# RV-3028.net
KiCad netlist of a schematic drawn in Altium Designer
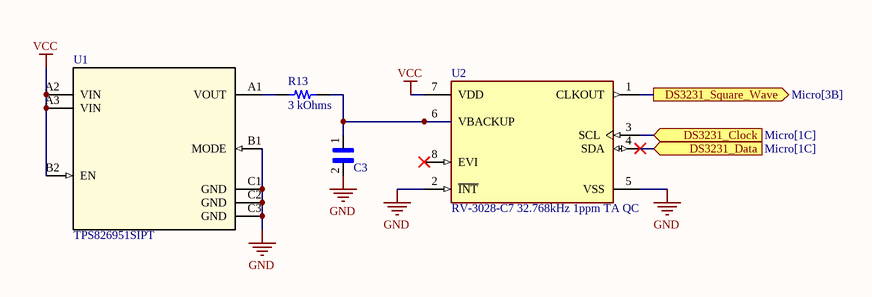
[diagram p0: RV-3028.SchDoc]

(export (version "E")
  (design (tool "Eeschema 10.0.6"))
  (components
    (comp (ref "C3")
      (value "CPX3225A752D")
      (footprint "CAPCP3225X100N")
      (description "7.5mF (EDLC) Supercapacitor 2.6V 1210 (3225 Metric) 25Ohm @ 1kHz")
      (fields (field (name "MF") "Seiko Instruments"))
      (libsource (lib "CPX3225A752D") (part "CPX3225A752D"))
    )
    (comp (ref "R13")
      (value "3 kOhms")
      (footprint "RES 0402_1005")
      (description "RES 3K OHM 1% 1/16W 0402")
      (fields (field (name "PART NUMBER") "RC0402FR-073KL") (field (name "MANUFACTURER") "Yageo"))
      (libsource (lib "Celestial Altium Library - altium_library") (part "Resistor"))
    )
    (comp (ref "U1")
      (value "TPS826951SIPT")
      (footprint "SIP0008A")
      (description "No Description Available")
      (fields (field (name "COPYRIGHT") "Copyright (C) 2022 Ultra Librarian. All rights reserved."))
      (libsource (lib "Schlib1") (part "TPS826951SIPT"))
    )
    (comp (ref "U2")
      (value "RV-3028-C7 32.768kHz 1ppm TA QC")
      (footprint "FP-RV-3028-C7_32_768kHz_1-MFG")
      (description "Real Time Clock Serial 2byte Clock/Calendar/Alarm/Timer/Battery Backup 8-Pin CSMD T/R")
      (fields
        (field (name "OCTOPART") "https://octopart.com/rv-3028-c7+32.768khz+1ppm+ta+qc-micro+crystal-98880451")
        (field (name "MANUFACTURER") "Micro Crystal")
      )
      (libsource (lib "Altium Content Vault") (part "f06799675b941e5ee1fb77ef065374c"))
    )
  )
  (nets
    (net (code "1") (name "/DS3231_Clock") (class "Default")
      (node (ref "U2") (pin "3") (pinfunction "SCL_3") (pintype "input"))
    )
    (net (code "2") (name "/DS3231_Data") (class "Default")
      (node (ref "U2") (pin "4") (pinfunction "SDA_4") (pintype "bidirectional+no_connect"))
    )
    (net (code "3") (name "/DS3231_Square_Wave") (class "Default")
      (node (ref "U2") (pin "1") (pinfunction "CLKOUT_1") (pintype "output"))
    )
    (net (code "4") (name "GND") (class "Default")
      (node (ref "C3") (pin "2") (pinfunction "2_2") (pintype "passive"))
      (node (ref "U1") (pin "B1") (pinfunction "MODE_B1") (pintype "input"))
      (node (ref "U1") (pin "C1") (pinfunction "GND_C1") (pintype "power_in"))
      (node (ref "U1") (pin "C2") (pinfunction "GND_C2") (pintype "power_in"))
      (node (ref "U1") (pin "C3") (pinfunction "GND_C3") (pintype "power_in"))
      (node (ref "U2") (pin "2") (pinfunction "~{INT}_2") (pintype "input"))
      (node (ref "U2") (pin "5") (pinfunction "VSS_5") (pintype "power_in"))
    )
    (net (code "5") (name "Net-(U1-VOUT)") (class "Default")
      (node (ref "R13") (pin "1") (pinfunction "1_1") (pintype "passive"))
      (node (ref "U1") (pin "A1") (pinfunction "VOUT_A1") (pintype "power_in"))
    )
    (net (code "6") (name "Net-(U2-VBACKUP)") (class "Default")
      (node (ref "C3") (pin "1") (pinfunction "1_1") (pintype "passive"))
      (node (ref "R13") (pin "2") (pinfunction "2_2") (pintype "passive"))
      (node (ref "U2") (pin "6") (pinfunction "VBACKUP_6") (pintype "power_in"))
    )
    (net (code "7") (name "VCC") (class "Default")
      (node (ref "U1") (pin "A2") (pinfunction "VIN_A2") (pintype "power_in"))
      (node (ref "U1") (pin "A3") (pinfunction "VIN_A3") (pintype "power_in"))
      (node (ref "U1") (pin "B2") (pinfunction "EN_B2") (pintype "input"))
      (node (ref "U2") (pin "7") (pinfunction "VDD_7") (pintype "power_in"))
    )
    (net (code "8") (name "unconnected-(U2-EVI-Pad8)") (class "Default")
      (node (ref "U2") (pin "8") (pinfunction "EVI_8") (pintype "input+no_connect"))
    )
  )
)
